# stm32-power.net
KiCad netlist of a schematic drawn in Altium Designer
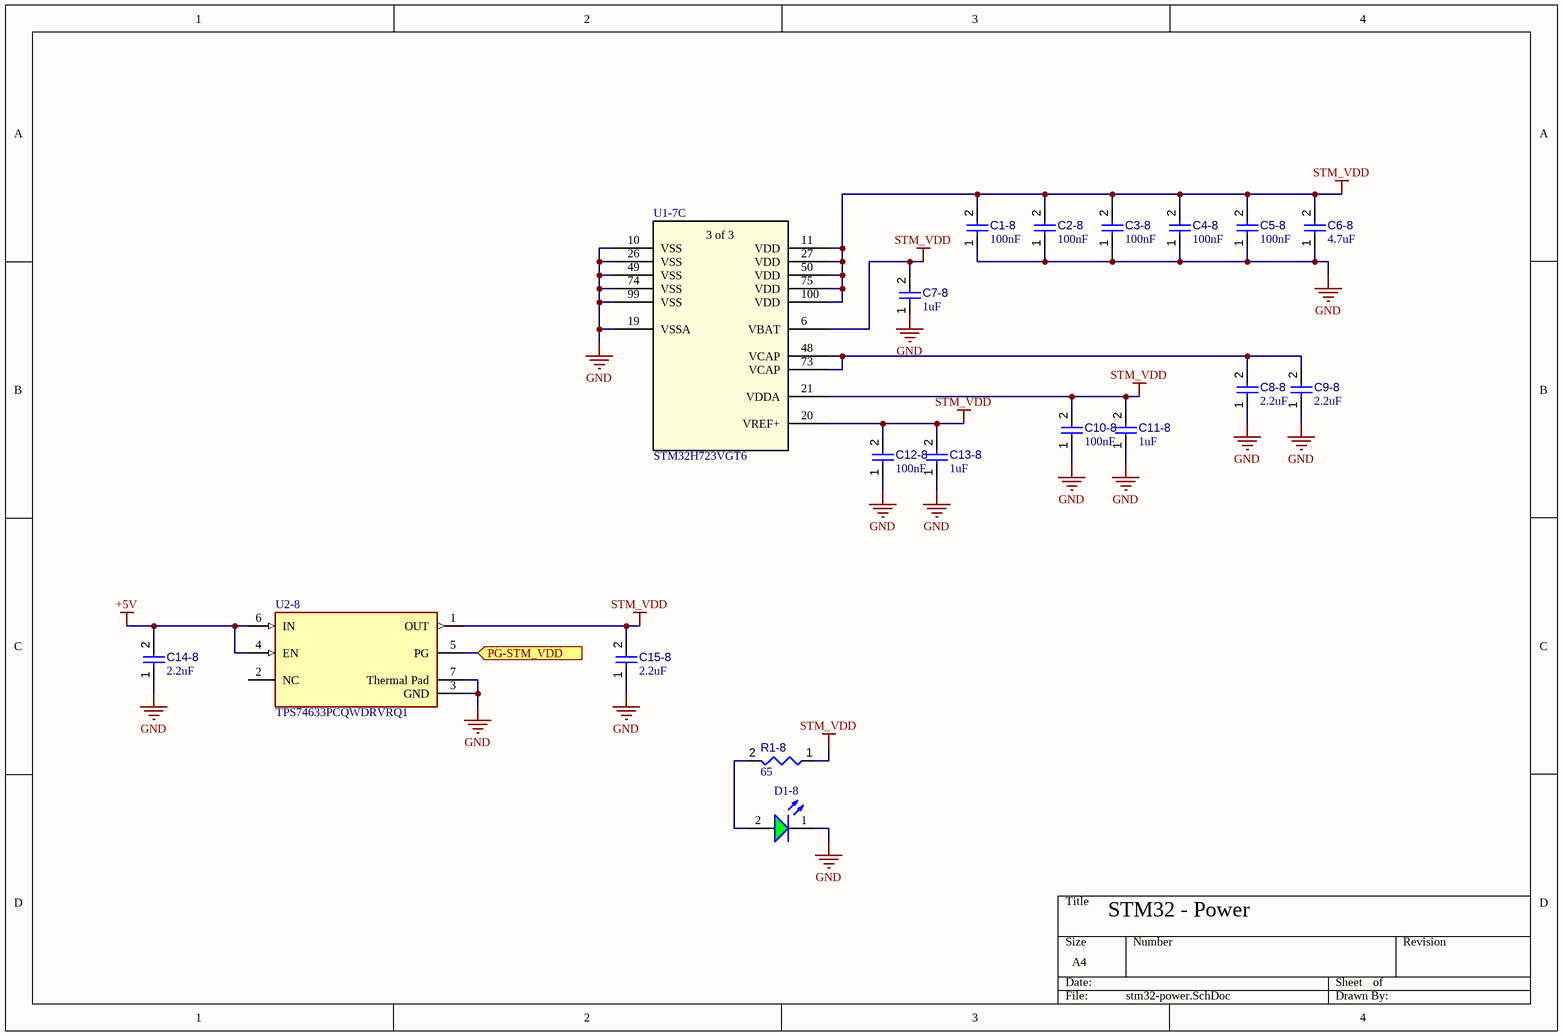
[diagram p0: stm32-power.SchDoc]

(export (version "E")
  (design (tool "Eeschema 10.0.6"))
  (components
    (comp (ref "C1-8")
      (value "100nF")
      (footprint "CAPC1608X94X35NL15T15")
      (fields (field (name "TOLERANCE") "10%") (field (name "Comment") "100nF 0603"))
      (libsource (lib "Michal") (part "CAP-NP-2"))
    )
    (comp (ref "C2-8")
      (value "100nF")
      (footprint "CAPC1608X94X35NL15T15")
      (fields (field (name "TOLERANCE") "10%") (field (name "Comment") "100nF 0603"))
      (libsource (lib "Michal") (part "CAP-NP-2"))
    )
    (comp (ref "C3-8")
      (value "100nF")
      (footprint "CAPC1608X94X35NL15T15")
      (fields (field (name "TOLERANCE") "10%") (field (name "Comment") "100nF 0603"))
      (libsource (lib "Michal") (part "CAP-NP-2"))
    )
    (comp (ref "C4-8")
      (value "100nF")
      (footprint "CAPC1608X94X35NL15T15")
      (fields (field (name "TOLERANCE") "10%") (field (name "Comment") "100nF 0603"))
      (libsource (lib "Michal") (part "CAP-NP-2"))
    )
    (comp (ref "C5-8")
      (value "100nF")
      (footprint "CAPC1608X94X35NL15T15")
      (fields (field (name "TOLERANCE") "10%") (field (name "Comment") "100nF 0603"))
      (libsource (lib "Michal") (part "CAP-NP-2"))
    )
    (comp (ref "C6-8")
      (value "4.7uF")
      (footprint "CAPC1608X94X35NL15T15")
      (fields (field (name "TOLERANCE") "10%"))
      (libsource (lib "Michal") (part "CAP-NP-2"))
    )
    (comp (ref "C7-8")
      (value "1uF")
      (footprint "CAPC1608X94X35NL15T15")
      (fields (field (name "TOLERANCE") "10%") (field (name "Comment") "1uF 0603"))
      (libsource (lib "Michal") (part "CAP-NP-2"))
    )
    (comp (ref "C8-8")
      (value "2.2uF")
      (footprint "CAPC1608X94X35NL15T15")
      (fields (field (name "TOLERANCE") "10%") (field (name "Comment") "2.2uF 0603"))
      (libsource (lib "Michal") (part "CAP-NP-2"))
    )
    (comp (ref "C9-8")
      (value "2.2uF")
      (footprint "CAPC1608X94X35NL15T15")
      (fields (field (name "TOLERANCE") "10%") (field (name "Comment") "2.2uF 0603"))
      (libsource (lib "Michal") (part "CAP-NP-2"))
    )
    (comp (ref "C10-8")
      (value "100nF")
      (footprint "CAPC1608X94X35NL15T15")
      (fields (field (name "TOLERANCE") "10%") (field (name "Comment") "100nF 0603"))
      (libsource (lib "Michal") (part "CAP-NP-2"))
    )
    (comp (ref "C11-8")
      (value "1uF")
      (footprint "CAPC1608X94X35NL15T15")
      (fields (field (name "TOLERANCE") "10%") (field (name "Comment") "1uF 0603"))
      (libsource (lib "Michal") (part "CAP-NP-2"))
    )
    (comp (ref "C12-8")
      (value "100nF")
      (footprint "CAPC1608X94X35NL15T15")
      (fields (field (name "TOLERANCE") "10%") (field (name "Comment") "100nF 0603"))
      (libsource (lib "Michal") (part "CAP-NP-2"))
    )
    (comp (ref "C13-8")
      (value "1uF")
      (footprint "CAPC1608X94X35NL15T15")
      (fields (field (name "TOLERANCE") "10%") (field (name "Comment") "1uF 0603"))
      (libsource (lib "Michal") (part "CAP-NP-2"))
    )
    (comp (ref "C14-8")
      (value "2.2uF")
      (footprint "CAPC1608X94X35NL15T15")
      (fields (field (name "TOLERANCE") "10%") (field (name "Comment") "2.2uF 0603"))
      (libsource (lib "Michal") (part "CAP-NP-2"))
    )
    (comp (ref "C15-8")
      (value "2.2uF")
      (footprint "CAPC1608X94X35NL15T15")
      (description "Chip Capacitor, 1 uF, +/- 10%, 16 V, 0603 (1608 Metric)")
      (fields (field (name "TOLERANCE") "10%") (field (name "Comment") "2.2uF 0603"))
      (libsource (lib "Michal") (part "CAP-NP-2"))
    )
    (comp (ref "D1-8")
      (value "150060VS75000")
      (footprint "WL-SMCW_0603_150060xx75000")
      (libsource (lib "Altium Content Vault") (part "LED_Green_2A-1K"))
    )
    (comp (ref "R1-8")
      (value "65")
      (footprint "RESC1608X55X25ML10T15")
      (description "Chip Resistor, 4.7 KOhm, +/- 1%, 0.1 W, -55 to 155 degC, 0603 (1608 Metric)")
      (fields (field (name "TOLERANCE") "1%") (field (name "POWER") "100mW"))
      (libsource (lib "Michal") (part "RES-2"))
    )
    (comp (ref "U1-7")
      (value "STM32H723VGT6")
      (footprint "LQFP100_STM")
      (description "No Description Available")
      (libsource (lib "STM32H723VGT6") (part "STM32H723VGT6"))
    )
    (comp (ref "U2-8")
      (value "TPS74633PCQWDRVRQ1")
      (footprint "FP-DRV0006C-IPC_C")
      (description "IC REG LINEAR 3.3V 1A 6WSON")
      (libsource (lib "Altium Content Vault") (part "1f5fe15cdb87ebf3bbd12d5f3fa30f5"))
    )
  )
  (nets
    (net (code "1") (name "+5V") (class "Default")
      (node (ref "C14-8") (pin "2") (pinfunction "2_2") (pintype "passive"))
      (node (ref "U2-8") (pin "4") (pinfunction "EN_4") (pintype "input"))
      (node (ref "U2-8") (pin "6") (pinfunction "IN_6") (pintype "input"))
    )
    (net (code "2") (name "/PG-STM_VDD") (class "Default")
      (node (ref "U2-8") (pin "5") (pinfunction "PG_5") (pintype "open_collector"))
    )
    (net (code "3") (name "GND") (class "Default")
      (node (ref "C1-8") (pin "1") (pinfunction "1_1") (pintype "passive"))
      (node (ref "C10-8") (pin "1") (pinfunction "1_1") (pintype "passive"))
      (node (ref "C11-8") (pin "1") (pinfunction "1_1") (pintype "passive"))
      (node (ref "C12-8") (pin "1") (pinfunction "1_1") (pintype "passive"))
      (node (ref "C13-8") (pin "1") (pinfunction "1_1") (pintype "passive"))
      (node (ref "C14-8") (pin "1") (pinfunction "1_1") (pintype "passive"))
      (node (ref "C15-8") (pin "1") (pinfunction "1_1") (pintype "passive"))
      (node (ref "C2-8") (pin "1") (pinfunction "1_1") (pintype "passive"))
      (node (ref "C3-8") (pin "1") (pinfunction "1_1") (pintype "passive"))
      (node (ref "C4-8") (pin "1") (pinfunction "1_1") (pintype "passive"))
      (node (ref "C5-8") (pin "1") (pinfunction "1_1") (pintype "passive"))
      (node (ref "C6-8") (pin "1") (pinfunction "1_1") (pintype "passive"))
      (node (ref "C7-8") (pin "1") (pinfunction "1_1") (pintype "passive"))
      (node (ref "C8-8") (pin "1") (pinfunction "1_1") (pintype "passive"))
      (node (ref "C9-8") (pin "1") (pinfunction "1_1") (pintype "passive"))
      (node (ref "D1-8") (pin "1") (pinfunction "K_1") (pintype "passive"))
      (node (ref "U1-7") (pin "10") (pinfunction "VSS_10") (pintype "power_in"))
      (node (ref "U1-7") (pin "19") (pinfunction "VSSA_19") (pintype "power_in"))
      (node (ref "U1-7") (pin "26") (pinfunction "VSS_26") (pintype "power_in"))
      (node (ref "U1-7") (pin "49") (pinfunction "VSS_49") (pintype "power_in"))
      (node (ref "U1-7") (pin "74") (pinfunction "VSS_74") (pintype "power_in"))
      (node (ref "U1-7") (pin "99") (pinfunction "VSS_99") (pintype "power_in"))
      (node (ref "U2-8") (pin "3") (pinfunction "GND_3") (pintype "power_in"))
      (node (ref "U2-8") (pin "7") (pinfunction "Thermal_Pad_7") (pintype "passive"))
    )
    (net (code "4") (name "Net-(C8-8-Pad2)") (class "Default")
      (node (ref "C8-8") (pin "2") (pinfunction "2_2") (pintype "passive"))
      (node (ref "C9-8") (pin "2") (pinfunction "2_2") (pintype "passive"))
      (node (ref "U1-7") (pin "48") (pinfunction "VCAP_48") (pintype "power_in"))
      (node (ref "U1-7") (pin "73") (pinfunction "VCAP_73") (pintype "power_in"))
    )
    (net (code "5") (name "Net-(D1-8-A)") (class "Default")
      (node (ref "D1-8") (pin "2") (pinfunction "A_2") (pintype "passive"))
      (node (ref "R1-8") (pin "2") (pinfunction "2_2") (pintype "passive"))
    )
    (net (code "6") (name "STM_VDD") (class "Default")
      (node (ref "C1-8") (pin "2") (pinfunction "2_2") (pintype "passive"))
      (node (ref "C10-8") (pin "2") (pinfunction "2_2") (pintype "passive"))
      (node (ref "C11-8") (pin "2") (pinfunction "2_2") (pintype "passive"))
      (node (ref "C12-8") (pin "2") (pinfunction "2_2") (pintype "passive"))
      (node (ref "C13-8") (pin "2") (pinfunction "2_2") (pintype "passive"))
      (node (ref "C15-8") (pin "2") (pinfunction "2_2") (pintype "passive"))
      (node (ref "C2-8") (pin "2") (pinfunction "2_2") (pintype "passive"))
      (node (ref "C3-8") (pin "2") (pinfunction "2_2") (pintype "passive"))
      (node (ref "C4-8") (pin "2") (pinfunction "2_2") (pintype "passive"))
      (node (ref "C5-8") (pin "2") (pinfunction "2_2") (pintype "passive"))
      (node (ref "C6-8") (pin "2") (pinfunction "2_2") (pintype "passive"))
      (node (ref "C7-8") (pin "2") (pinfunction "2_2") (pintype "passive"))
      (node (ref "R1-8") (pin "1") (pinfunction "1_1") (pintype "passive"))
      (node (ref "U1-7") (pin "100") (pinfunction "VDD_100") (pintype "power_in"))
      (node (ref "U1-7") (pin "11") (pinfunction "VDD_11") (pintype "power_in"))
      (node (ref "U1-7") (pin "20") (pinfunction "VREF+_20") (pintype "power_in"))
      (node (ref "U1-7") (pin "21") (pinfunction "VDDA_21") (pintype "power_in"))
      (node (ref "U1-7") (pin "27") (pinfunction "VDD_27") (pintype "power_in"))
      (node (ref "U1-7") (pin "50") (pinfunction "VDD_50") (pintype "power_in"))
      (node (ref "U1-7") (pin "6") (pinfunction "VBAT_6") (pintype "power_in"))
      (node (ref "U1-7") (pin "75") (pinfunction "VDD_75") (pintype "power_in"))
      (node (ref "U2-8") (pin "1") (pinfunction "OUT_1") (pintype "output"))
    )
    (net (code "7") (name "unconnected-(U2-8-NC-Pad2)") (class "Default")
      (node (ref "U2-8") (pin "2") (pinfunction "NC_2") (pintype "passive"))
    )
  )
)
